# R7FA2E1A7_SCI_SPI.net
KiCad netlist of a schematic drawn in EasyEDA Pro
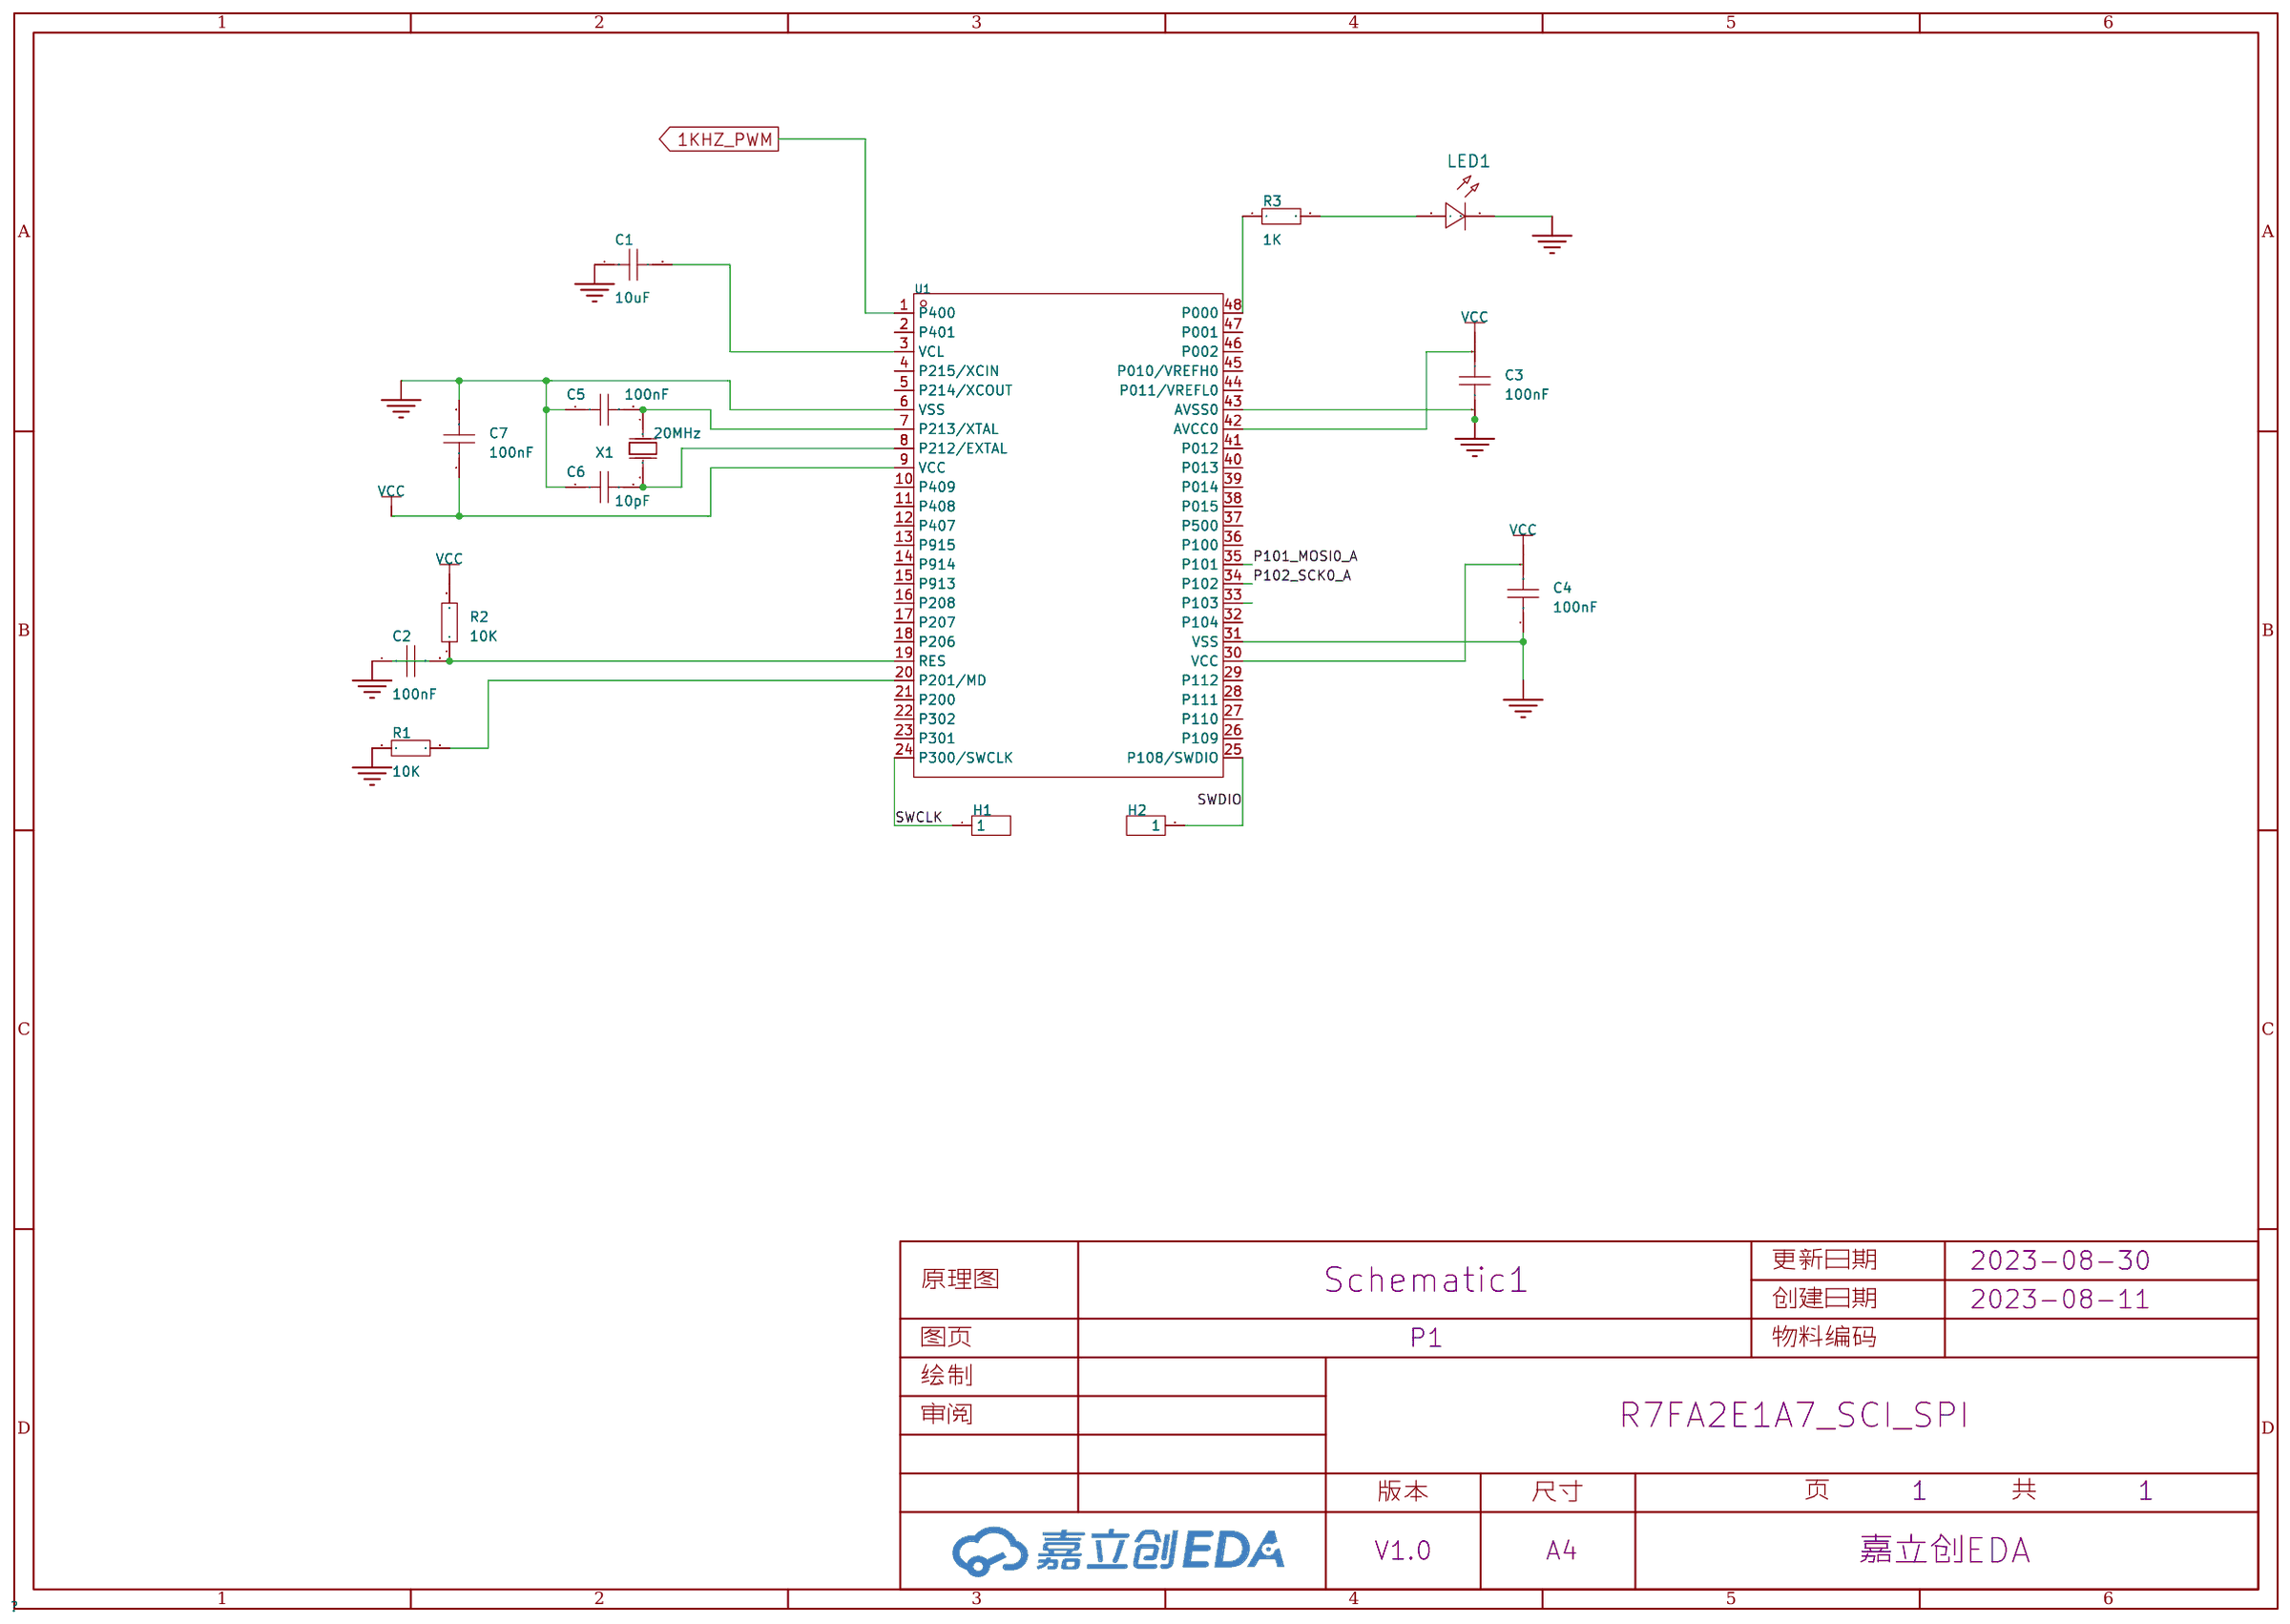
[diagram p0: schematic sheet]

(export (version "E")
  (design (tool "Eeschema 10.0.6"))
  (components
    (comp (ref "C1")
      (value "10uF")
      (footprint "easyedapro:C0603")
      (libsource (lib "easyedapro") (part "CapAcitance"))
    )
    (comp (ref "C2")
      (value "100nF")
      (footprint "easyedapro:C0603")
      (libsource (lib "easyedapro") (part "CapAcitance"))
    )
    (comp (ref "C3")
      (value "100nF")
      (footprint "easyedapro:C0603")
      (libsource (lib "easyedapro") (part "CapAcitance"))
    )
    (comp (ref "C4")
      (value "100nF")
      (footprint "easyedapro:C0603")
      (libsource (lib "easyedapro") (part "CapAcitance"))
    )
    (comp (ref "C5")
      (value "100nF")
      (footprint "easyedapro:C0603")
      (libsource (lib "easyedapro") (part "CapAcitance"))
    )
    (comp (ref "C6")
      (value "10pF")
      (footprint "easyedapro:C0603")
      (libsource (lib "easyedapro") (part "CapAcitance"))
    )
    (comp (ref "C7")
      (value "100nF")
      (footprint "easyedapro:C0603")
      (libsource (lib "easyedapro") (part "CapAcitance"))
    )
    (comp (ref "H1")
      (value "~")
      (footprint "easyedapro:HDR-TH_1P-V-M_XKB_X4611WV-01I-C28D40")
      (libsource (lib "easyedapro") (part "HDR_1x1"))
    )
    (comp (ref "H2")
      (value "~")
      (footprint "easyedapro:HDR-TH_1P-V-M_XKB_X4611WV-01I-C28D40")
      (libsource (lib "easyedapro") (part "HDR_1x1"))
    )
    (comp (ref "LED1")
      (value "~")
      (footprint "easyedapro:LED_0603")
      (libsource (lib "easyedapro") (part "LED_R"))
    )
    (comp (ref "R1") (value "10K") (footprint "easyedapro:R0603") (libsource (lib "easyedapro") (part "电阻")))
    (comp (ref "R2") (value "10K") (footprint "easyedapro:R0603") (libsource (lib "easyedapro") (part "电阻")))
    (comp (ref "R3") (value "1K") (footprint "easyedapro:R0603") (libsource (lib "easyedapro") (part "电阻")))
    (comp (ref "U1")
      (value "R7FA2E1A72DFL#AA0")
      (footprint "easyedapro:LQFP-48_L7.0-W7.0-P0.50-LS9.0-BL")
      (description "CPU内核:ARM Cortex-M23;CPU最大主频:48MHz;工作电压范围:1.6V~5.5V;程序存储容量:64KB;RAM总容量:16KB;GPIO端口数量:40;")
      (fields (field (name "Manufacturer") "RENESAS(瑞萨)/IDT"))
      (libsource (lib "easyedapro") (part "R7FA2E1A72DFL#AA0"))
    )
    (comp (ref "X1")
      (value "20MHz")
      (footprint "easyedapro:OSC-TH_L10.0-W4.5-P5.00")
      (description "频率:20MHz;频率公差:±10ppm;负载电容:15pF;")
      (fields (field (name "Manufacturer Part") "X49SD20MPB2SC") (field (name "Manufacturer") "YXC(扬兴晶振)"))
      (libsource (lib "easyedapro") (part "X49SD20MPB2SC"))
    )
  )
  (nets
    (net (code "1") (name "/P101_MOSI0_A") (class "Default")
      (node (ref "U1") (pin "35") (pinfunction "P101_35") (pintype "input"))
    )
    (net (code "2") (name "/P102_SCK0_A") (class "Default")
      (node (ref "U1") (pin "34") (pinfunction "P102_34") (pintype "input"))
    )
    (net (code "3") (name "/SWCLK") (class "Default")
      (node (ref "H1") (pin "1") (pinfunction "1_1") (pintype "unspecified"))
      (node (ref "U1") (pin "24") (pinfunction "P300/SWCLK_24") (pintype "input"))
    )
    (net (code "4") (name "/SWDIO") (class "Default")
      (node (ref "H2") (pin "1") (pinfunction "1_1") (pintype "unspecified"))
      (node (ref "U1") (pin "25") (pinfunction "P108/SWDIO_25") (pintype "input"))
    )
    (net (code "5") (name "1KHZ_PWM") (class "Default")
      (node (ref "U1") (pin "1") (pinfunction "P400_1") (pintype "input"))
    )
    (net (code "6") (name "GND") (class "Default")
      (node (ref "C1") (pin "1") (pinfunction "1_1") (pintype "input"))
      (node (ref "C2") (pin "1") (pinfunction "1_1") (pintype "input"))
      (node (ref "C3") (pin "1") (pinfunction "1_1") (pintype "input"))
      (node (ref "C4") (pin "1") (pinfunction "1_1") (pintype "input"))
      (node (ref "C5") (pin "1") (pinfunction "1_1") (pintype "input"))
      (node (ref "C6") (pin "1") (pinfunction "1_1") (pintype "input"))
      (node (ref "C7") (pin "2") (pinfunction "2_2") (pintype "input"))
      (node (ref "LED1") (pin "1") (pinfunction "C_1") (pintype "input"))
      (node (ref "R1") (pin "1") (pinfunction "1_1") (pintype "input"))
      (node (ref "U1") (pin "31") (pinfunction "VSS_31") (pintype "input"))
      (node (ref "U1") (pin "43") (pinfunction "AVSS0_43") (pintype "input"))
      (node (ref "U1") (pin "6") (pinfunction "VSS_6") (pintype "input"))
    )
    (net (code "7") (name "Net-(LED1-A)") (class "Default")
      (node (ref "LED1") (pin "2") (pinfunction "A_2") (pintype "input"))
      (node (ref "R3") (pin "2") (pinfunction "2_2") (pintype "input"))
    )
    (net (code "8") (name "Net-(U1-P000)") (class "Default")
      (node (ref "R3") (pin "1") (pinfunction "1_1") (pintype "input"))
      (node (ref "U1") (pin "48") (pinfunction "P000_48") (pintype "input"))
    )
    (net (code "9") (name "Net-(U1-P201{slash}MD)") (class "Default")
      (node (ref "R1") (pin "2") (pinfunction "2_2") (pintype "input"))
      (node (ref "U1") (pin "20") (pinfunction "P201/MD_20") (pintype "input"))
    )
    (net (code "10") (name "Net-(U1-P212{slash}EXTAL)") (class "Default")
      (node (ref "C6") (pin "2") (pinfunction "2_2") (pintype "input"))
      (node (ref "U1") (pin "8") (pinfunction "P212/EXTAL_8") (pintype "input"))
      (node (ref "X1") (pin "2") (pinfunction "OSC2_2") (pintype "input"))
    )
    (net (code "11") (name "Net-(U1-P213{slash}XTAL)") (class "Default")
      (node (ref "C5") (pin "2") (pinfunction "2_2") (pintype "input"))
      (node (ref "U1") (pin "7") (pinfunction "P213/XTAL_7") (pintype "input"))
      (node (ref "X1") (pin "1") (pinfunction "OSC1_1") (pintype "input"))
    )
    (net (code "12") (name "Net-(U1-RES)") (class "Default")
      (node (ref "C2") (pin "2") (pinfunction "2_2") (pintype "input"))
      (node (ref "R2") (pin "1") (pinfunction "1_1") (pintype "input"))
      (node (ref "U1") (pin "19") (pinfunction "RES_19") (pintype "input"))
    )
    (net (code "13") (name "Net-(U1-VCL)") (class "Default")
      (node (ref "C1") (pin "2") (pinfunction "2_2") (pintype "input"))
      (node (ref "U1") (pin "3") (pinfunction "VCL_3") (pintype "input"))
    )
    (net (code "14") (name "VCC") (class "Default")
      (node (ref "C3") (pin "2") (pinfunction "2_2") (pintype "input"))
      (node (ref "C4") (pin "2") (pinfunction "2_2") (pintype "input"))
      (node (ref "C7") (pin "1") (pinfunction "1_1") (pintype "input"))
      (node (ref "R2") (pin "2") (pinfunction "2_2") (pintype "input"))
      (node (ref "U1") (pin "9") (pinfunction "VCC_9") (pintype "input"))
    )
    (net (code "15") (name "unconnected-(U1-AVCC0-Pad42)") (class "Default")
      (node (ref "U1") (pin "42") (pinfunction "AVCC0_42") (pintype "input"))
    )
    (net (code "16") (name "unconnected-(U1-P001-Pad47)") (class "Default")
      (node (ref "U1") (pin "47") (pinfunction "P001_47") (pintype "input"))
    )
    (net (code "17") (name "unconnected-(U1-P002-Pad46)") (class "Default")
      (node (ref "U1") (pin "46") (pinfunction "P002_46") (pintype "input"))
    )
    (net (code "18") (name "unconnected-(U1-P010{slash}VREFH0-Pad45)") (class "Default")
      (node (ref "U1") (pin "45") (pinfunction "P010/VREFH0_45") (pintype "input"))
    )
    (net (code "19") (name "unconnected-(U1-P011{slash}VREFL0-Pad44)") (class "Default")
      (node (ref "U1") (pin "44") (pinfunction "P011/VREFL0_44") (pintype "input"))
    )
    (net (code "20") (name "unconnected-(U1-P012-Pad41)") (class "Default")
      (node (ref "U1") (pin "41") (pinfunction "P012_41") (pintype "input"))
    )
    (net (code "21") (name "unconnected-(U1-P013-Pad40)") (class "Default")
      (node (ref "U1") (pin "40") (pinfunction "P013_40") (pintype "input"))
    )
    (net (code "22") (name "unconnected-(U1-P014-Pad39)") (class "Default")
      (node (ref "U1") (pin "39") (pinfunction "P014_39") (pintype "input"))
    )
    (net (code "23") (name "unconnected-(U1-P015-Pad38)") (class "Default")
      (node (ref "U1") (pin "38") (pinfunction "P015_38") (pintype "input"))
    )
    (net (code "24") (name "unconnected-(U1-P100-Pad36)") (class "Default")
      (node (ref "U1") (pin "36") (pinfunction "P100_36") (pintype "input"))
    )
    (net (code "25") (name "unconnected-(U1-P103-Pad33)") (class "Default")
      (node (ref "U1") (pin "33") (pinfunction "P103_33") (pintype "input"))
    )
    (net (code "26") (name "unconnected-(U1-P104-Pad32)") (class "Default")
      (node (ref "U1") (pin "32") (pinfunction "P104_32") (pintype "input"))
    )
    (net (code "27") (name "unconnected-(U1-P109-Pad26)") (class "Default")
      (node (ref "U1") (pin "26") (pinfunction "P109_26") (pintype "input"))
    )
    (net (code "28") (name "unconnected-(U1-P110-Pad27)") (class "Default")
      (node (ref "U1") (pin "27") (pinfunction "P110_27") (pintype "input"))
    )
    (net (code "29") (name "unconnected-(U1-P111-Pad28)") (class "Default")
      (node (ref "U1") (pin "28") (pinfunction "P111_28") (pintype "input"))
    )
    (net (code "30") (name "unconnected-(U1-P112-Pad29)") (class "Default")
      (node (ref "U1") (pin "29") (pinfunction "P112_29") (pintype "input"))
    )
    (net (code "31") (name "unconnected-(U1-P200-Pad21)") (class "Default")
      (node (ref "U1") (pin "21") (pinfunction "P200_21") (pintype "input"))
    )
    (net (code "32") (name "unconnected-(U1-P206-Pad18)") (class "Default")
      (node (ref "U1") (pin "18") (pinfunction "P206_18") (pintype "input"))
    )
    (net (code "33") (name "unconnected-(U1-P207-Pad17)") (class "Default")
      (node (ref "U1") (pin "17") (pinfunction "P207_17") (pintype "input"))
    )
    (net (code "34") (name "unconnected-(U1-P208-Pad16)") (class "Default")
      (node (ref "U1") (pin "16") (pinfunction "P208_16") (pintype "input"))
    )
    (net (code "35") (name "unconnected-(U1-P214{slash}XCOUT-Pad5)") (class "Default")
      (node (ref "U1") (pin "5") (pinfunction "P214/XCOUT_5") (pintype "input"))
    )
    (net (code "36") (name "unconnected-(U1-P215{slash}XCIN-Pad4)") (class "Default")
      (node (ref "U1") (pin "4") (pinfunction "P215/XCIN_4") (pintype "input"))
    )
    (net (code "37") (name "unconnected-(U1-P301-Pad23)") (class "Default")
      (node (ref "U1") (pin "23") (pinfunction "P301_23") (pintype "input"))
    )
    (net (code "38") (name "unconnected-(U1-P302-Pad22)") (class "Default")
      (node (ref "U1") (pin "22") (pinfunction "P302_22") (pintype "input"))
    )
    (net (code "39") (name "unconnected-(U1-P401-Pad2)") (class "Default")
      (node (ref "U1") (pin "2") (pinfunction "P401_2") (pintype "input"))
    )
    (net (code "40") (name "unconnected-(U1-P407-Pad12)") (class "Default")
      (node (ref "U1") (pin "12") (pinfunction "P407_12") (pintype "input"))
    )
    (net (code "41") (name "unconnected-(U1-P408-Pad11)") (class "Default")
      (node (ref "U1") (pin "11") (pinfunction "P408_11") (pintype "input"))
    )
    (net (code "42") (name "unconnected-(U1-P409-Pad10)") (class "Default")
      (node (ref "U1") (pin "10") (pinfunction "P409_10") (pintype "input"))
    )
    (net (code "43") (name "unconnected-(U1-P500-Pad37)") (class "Default")
      (node (ref "U1") (pin "37") (pinfunction "P500_37") (pintype "input"))
    )
    (net (code "44") (name "unconnected-(U1-P913-Pad15)") (class "Default")
      (node (ref "U1") (pin "15") (pinfunction "P913_15") (pintype "input"))
    )
    (net (code "45") (name "unconnected-(U1-P914-Pad14)") (class "Default")
      (node (ref "U1") (pin "14") (pinfunction "P914_14") (pintype "input"))
    )
    (net (code "46") (name "unconnected-(U1-P915-Pad13)") (class "Default")
      (node (ref "U1") (pin "13") (pinfunction "P915_13") (pintype "input"))
    )
    (net (code "47") (name "unconnected-(U1-VCC-Pad30)") (class "Default")
      (node (ref "U1") (pin "30") (pinfunction "VCC_30") (pintype "input"))
    )
  )
)
